# 04-Control_Circuit.net
KiCad netlist of a schematic drawn in Altium Designer
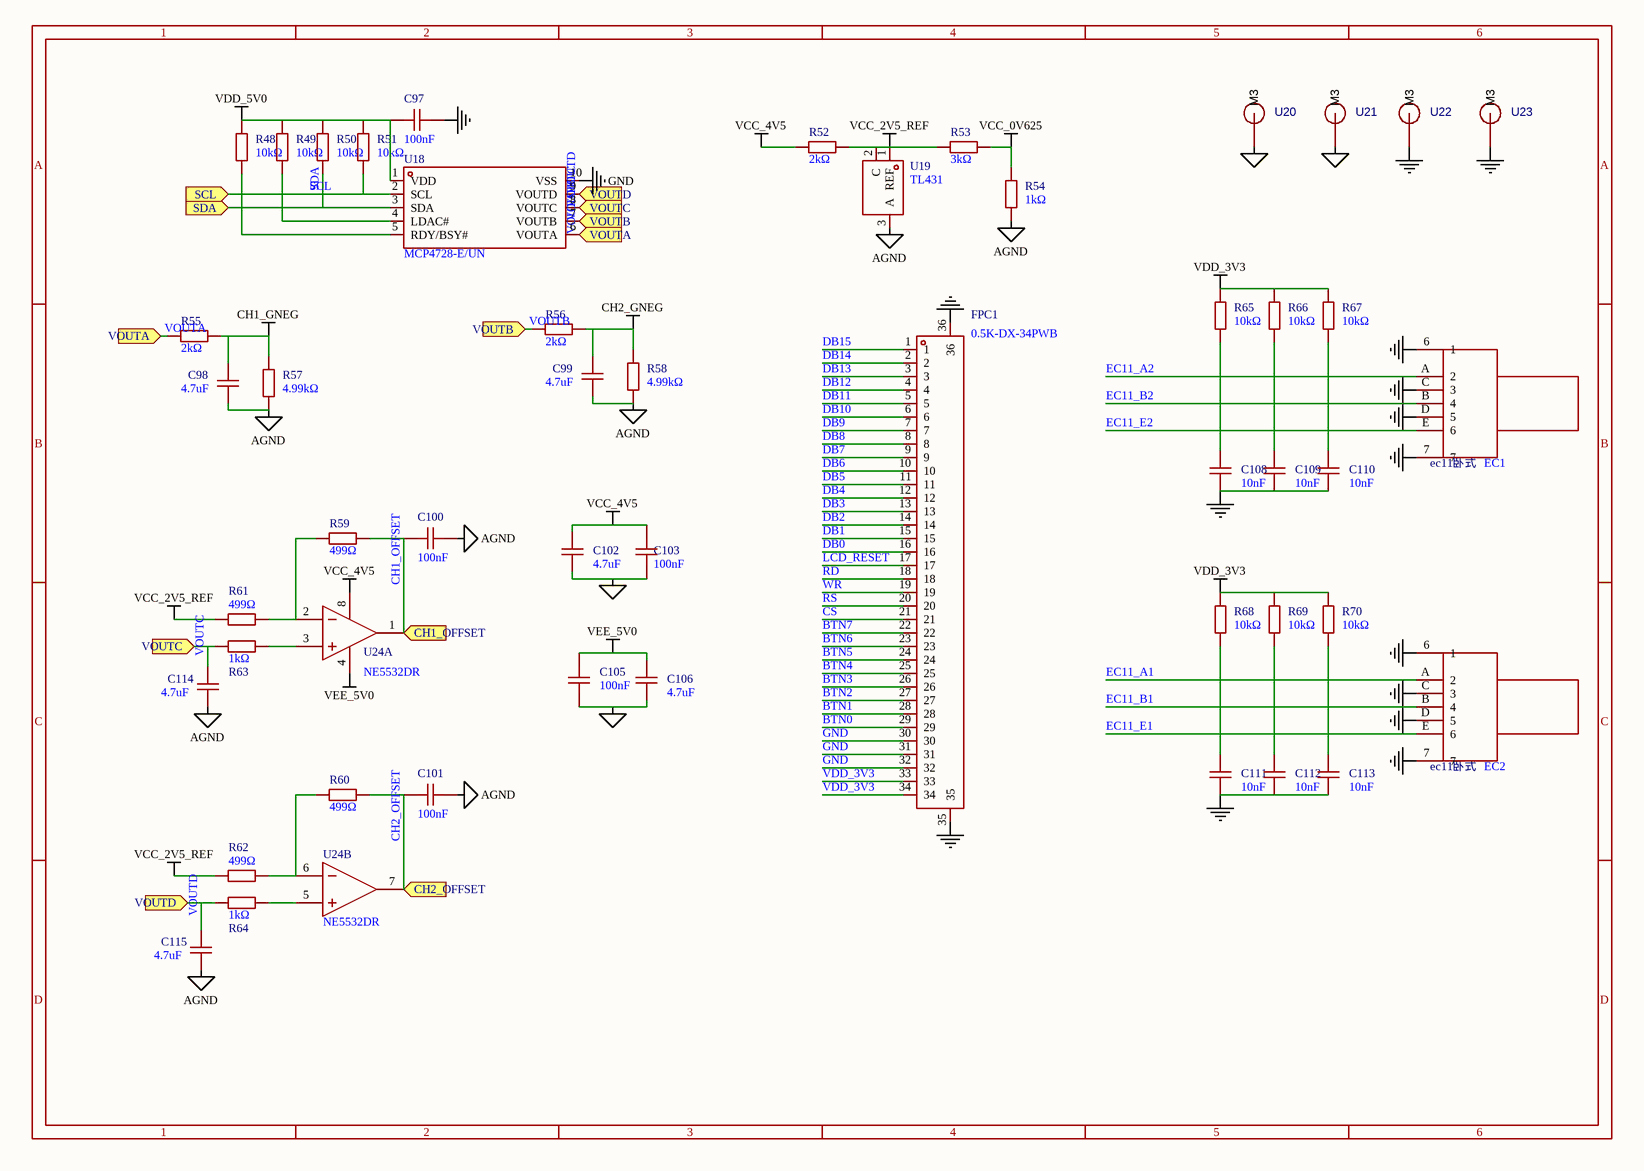
[diagram p0: 04-Control Circuit.schdoc]

(export (version "E")
  (design (tool "Eeschema 10.0.6"))
  (components
    (comp (ref "C97")
      (value "100nF")
      (footprint "C0603")
      (fields
        (field (name "MANUFACTURER") "HRE(芯声)")
        (field (name "MANUFACTURER PART") "CGA0603X7R104K500JT")
        (field (name "TOLERANCE") "±10%")
      )
      (libsource (lib "altium-import") (part "root_2_CGA0603X7R104K500JT_"))
    )
    (comp (ref "C98")
      (value "4.7uF")
      (footprint "C0603")
      (fields
        (field (name "MANUFACTURER") "SAMSUNG(三星)")
        (field (name "MANUFACTURER PART") "CL10A475KO8NNNC")
        (field (name "TOLERANCE") "±10%")
      )
      (libsource (lib "altium-import") (part "root_1_CL10A475KO8NNNC_"))
    )
    (comp (ref "C99")
      (value "4.7uF")
      (footprint "C0603")
      (fields
        (field (name "MANUFACTURER") "SAMSUNG(三星)")
        (field (name "MANUFACTURER PART") "CL10A475KO8NNNC")
        (field (name "TOLERANCE") "±10%")
      )
      (libsource (lib "altium-import") (part "root_1_CL10A475KO8NNNC_"))
    )
    (comp (ref "C100")
      (value "100nF")
      (footprint "C0603")
      (fields
        (field (name "MANUFACTURER") "HRE(芯声)")
        (field (name "MANUFACTURER PART") "CGA0603X7R104K500JT")
        (field (name "TOLERANCE") "±10%")
      )
      (libsource (lib "altium-import") (part "root_2_CGA0603X7R104K500JT_"))
    )
    (comp (ref "C101")
      (value "100nF")
      (footprint "C0603")
      (fields
        (field (name "MANUFACTURER") "HRE(芯声)")
        (field (name "MANUFACTURER PART") "CGA0603X7R104K500JT")
        (field (name "TOLERANCE") "±10%")
      )
      (libsource (lib "altium-import") (part "root_2_CGA0603X7R104K500JT_"))
    )
    (comp (ref "C102")
      (value "4.7uF")
      (footprint "C0603")
      (fields
        (field (name "MANUFACTURER") "SAMSUNG(三星)")
        (field (name "MANUFACTURER PART") "CL10A475KO8NNNC")
        (field (name "TOLERANCE") "±10%")
      )
      (libsource (lib "altium-import") (part "root_1_CL10A475KO8NNNC_"))
    )
    (comp (ref "C103")
      (value "100nF")
      (footprint "C0603")
      (fields
        (field (name "MANUFACTURER") "HRE(芯声)")
        (field (name "MANUFACTURER PART") "CGA0603X7R104K500JT")
        (field (name "TOLERANCE") "±10%")
      )
      (libsource (lib "altium-import") (part "root_1_CGA0603X7R104K500JT_"))
    )
    (comp (ref "C105")
      (value "100nF")
      (footprint "C0603")
      (fields
        (field (name "MANUFACTURER") "HRE(芯声)")
        (field (name "MANUFACTURER PART") "CGA0603X7R104K500JT")
        (field (name "TOLERANCE") "±10%")
      )
      (libsource (lib "altium-import") (part "root_1_CGA0603X7R104K500JT_"))
    )
    (comp (ref "C106")
      (value "4.7uF")
      (footprint "C0603")
      (fields
        (field (name "MANUFACTURER") "SAMSUNG(三星)")
        (field (name "MANUFACTURER PART") "CL10A475KO8NNNC")
        (field (name "TOLERANCE") "±10%")
      )
      (libsource (lib "altium-import") (part "root_1_CL10A475KO8NNNC_"))
    )
    (comp (ref "C108")
      (value "10nF")
      (footprint "C0603")
      (fields
        (field (name "MANUFACTURER") "YAGEO(国巨)")
        (field (name "MANUFACTURER PART") "CC0603KRX7R9BB103")
        (field (name "TOLERANCE") "±10%")
      )
      (libsource (lib "altium-import") (part "root_1_CC0603KRX7R9BB103_"))
    )
    (comp (ref "C109")
      (value "10nF")
      (footprint "C0603")
      (fields
        (field (name "MANUFACTURER") "YAGEO(国巨)")
        (field (name "MANUFACTURER PART") "CC0603KRX7R9BB103")
        (field (name "TOLERANCE") "±10%")
      )
      (libsource (lib "altium-import") (part "root_1_CC0603KRX7R9BB103_"))
    )
    (comp (ref "C110")
      (value "10nF")
      (footprint "C0603")
      (fields
        (field (name "MANUFACTURER") "YAGEO(国巨)")
        (field (name "MANUFACTURER PART") "CC0603KRX7R9BB103")
        (field (name "TOLERANCE") "±10%")
      )
      (libsource (lib "altium-import") (part "root_1_CC0603KRX7R9BB103_"))
    )
    (comp (ref "C111")
      (value "10nF")
      (footprint "C0603")
      (fields
        (field (name "MANUFACTURER") "YAGEO(国巨)")
        (field (name "MANUFACTURER PART") "CC0603KRX7R9BB103")
        (field (name "TOLERANCE") "±10%")
      )
      (libsource (lib "altium-import") (part "root_1_CC0603KRX7R9BB103_"))
    )
    (comp (ref "C112")
      (value "10nF")
      (footprint "C0603")
      (fields
        (field (name "MANUFACTURER") "YAGEO(国巨)")
        (field (name "MANUFACTURER PART") "CC0603KRX7R9BB103")
        (field (name "TOLERANCE") "±10%")
      )
      (libsource (lib "altium-import") (part "root_1_CC0603KRX7R9BB103_"))
    )
    (comp (ref "C113")
      (value "10nF")
      (footprint "C0603")
      (fields
        (field (name "MANUFACTURER") "YAGEO(国巨)")
        (field (name "MANUFACTURER PART") "CC0603KRX7R9BB103")
        (field (name "TOLERANCE") "±10%")
      )
      (libsource (lib "altium-import") (part "root_1_CC0603KRX7R9BB103_"))
    )
    (comp (ref "C114")
      (value "4.7uF")
      (footprint "C0603")
      (fields
        (field (name "MANUFACTURER") "SAMSUNG(三星)")
        (field (name "MANUFACTURER PART") "CL10A475KO8NNNC")
        (field (name "TOLERANCE") "±10%")
      )
      (libsource (lib "altium-import") (part "root_1_CL10A475KO8NNNC_"))
    )
    (comp (ref "C115")
      (value "4.7uF")
      (footprint "C0603")
      (fields
        (field (name "MANUFACTURER") "SAMSUNG(三星)")
        (field (name "MANUFACTURER PART") "CL10A475KO8NNNC")
        (field (name "TOLERANCE") "±10%")
      )
      (libsource (lib "altium-import") (part "root_1_CL10A475KO8NNNC_"))
    )
    (comp (ref "EC1")
      (value "~")
      (footprint "ec11卧式立式编码器")
      (fields (field (name "DEVICE") "ec11卧式"))
      (libsource (lib "altium-import") (part "root_0_ec11卧式_"))
    )
    (comp (ref "EC2")
      (value "~")
      (footprint "ec11卧式立式编码器")
      (fields (field (name "DEVICE") "ec11卧式"))
      (libsource (lib "altium-import") (part "root_0_ec11卧式_"))
    )
    (comp (ref "FPC1")
      (value "0.5K-DX-34PWB")
      (footprint "FPC-SMD_F0502-B-34-15T-R")
      (fields (field (name "MANUFACTURER") "HDGC(华德共创)"))
      (libsource (lib "altium-import") (part "root_0_0.5K-DX-34PWB_"))
    )
    (comp (ref "R48")
      (value "10kΩ")
      (footprint "R0603")
      (fields
        (field (name "MANUFACTURER") "UNI-ROYAL(厚声)")
        (field (name "MANUFACTURER PART") "0603WAF1002T5E")
        (field (name "TOLERANCE") "±1%")
      )
      (libsource (lib "altium-import") (part "root_1_0603WAF1002T5E_"))
    )
    (comp (ref "R49")
      (value "10kΩ")
      (footprint "R0603")
      (fields
        (field (name "MANUFACTURER") "UNI-ROYAL(厚声)")
        (field (name "MANUFACTURER PART") "0603WAF1002T5E")
        (field (name "TOLERANCE") "±1%")
      )
      (libsource (lib "altium-import") (part "root_1_0603WAF1002T5E_"))
    )
    (comp (ref "R50")
      (value "10kΩ")
      (footprint "R0603")
      (fields
        (field (name "MANUFACTURER") "UNI-ROYAL(厚声)")
        (field (name "MANUFACTURER PART") "0603WAF1002T5E")
        (field (name "TOLERANCE") "±1%")
      )
      (libsource (lib "altium-import") (part "root_1_0603WAF1002T5E_"))
    )
    (comp (ref "R51")
      (value "10kΩ")
      (footprint "R0603")
      (fields
        (field (name "MANUFACTURER") "UNI-ROYAL(厚声)")
        (field (name "MANUFACTURER PART") "0603WAF1002T5E")
        (field (name "TOLERANCE") "±1%")
      )
      (libsource (lib "altium-import") (part "root_1_0603WAF1002T5E_"))
    )
    (comp (ref "R52")
      (value "2kΩ")
      (footprint "R0603")
      (fields
        (field (name "MANUFACTURER") "UNI-ROYAL(厚声)")
        (field (name "MANUFACTURER PART") "0603WAF2001T5E")
        (field (name "TOLERANCE") "±1%")
      )
      (libsource (lib "altium-import") (part "root_2_0603WAF2001T5E_"))
    )
    (comp (ref "R53")
      (value "3kΩ")
      (footprint "R0603")
      (fields
        (field (name "MANUFACTURER") "UNI-ROYAL(厚声)")
        (field (name "MANUFACTURER PART") "0603WAF3001T5E")
        (field (name "TOLERANCE") "±1%")
      )
      (libsource (lib "altium-import") (part "root_0_0603WAF3001T5E_"))
    )
    (comp (ref "R54")
      (value "1kΩ")
      (footprint "R0603")
      (fields
        (field (name "MANUFACTURER") "UNI-ROYAL(厚声)")
        (field (name "MANUFACTURER PART") "0603WAF1001T5E")
        (field (name "TOLERANCE") "±1%")
      )
      (libsource (lib "altium-import") (part "root_1_0603WAF1001T5E_"))
    )
    (comp (ref "R55")
      (value "2kΩ")
      (footprint "R0603")
      (fields
        (field (name "MANUFACTURER") "UNI-ROYAL(厚声)")
        (field (name "MANUFACTURER PART") "0603WAF2001T5E")
        (field (name "TOLERANCE") "±1%")
      )
      (libsource (lib "altium-import") (part "root_2_0603WAF2001T5E_"))
    )
    (comp (ref "R56")
      (value "2kΩ")
      (footprint "R0603")
      (fields
        (field (name "MANUFACTURER") "UNI-ROYAL(厚声)")
        (field (name "MANUFACTURER PART") "0603WAF2001T5E")
        (field (name "TOLERANCE") "±1%")
      )
      (libsource (lib "altium-import") (part "root_2_0603WAF2001T5E_"))
    )
    (comp (ref "R57")
      (value "4.99kΩ")
      (footprint "R0603")
      (fields
        (field (name "MANUFACTURER") "UNI-ROYAL(厚声)")
        (field (name "MANUFACTURER PART") "0603WAF4991T5E")
        (field (name "TOLERANCE") "±1%")
      )
      (libsource (lib "altium-import") (part "root_1_0603WAF4991T5E_"))
    )
    (comp (ref "R58")
      (value "4.99kΩ")
      (footprint "R0603")
      (fields
        (field (name "MANUFACTURER") "UNI-ROYAL(厚声)")
        (field (name "MANUFACTURER PART") "0603WAF4991T5E")
        (field (name "TOLERANCE") "±1%")
      )
      (libsource (lib "altium-import") (part "root_1_0603WAF4991T5E_"))
    )
    (comp (ref "R59")
      (value "499Ω")
      (footprint "R0603")
      (fields
        (field (name "MANUFACTURER") "UNI-ROYAL(厚声)")
        (field (name "MANUFACTURER PART") "0603WAF4990T5E")
        (field (name "TOLERANCE") "±1%")
      )
      (libsource (lib "altium-import") (part "root_0_0603WAF4990T5E_"))
    )
    (comp (ref "R60")
      (value "499Ω")
      (footprint "R0603")
      (fields
        (field (name "MANUFACTURER") "UNI-ROYAL(厚声)")
        (field (name "MANUFACTURER PART") "0603WAF4990T5E")
        (field (name "TOLERANCE") "±1%")
      )
      (libsource (lib "altium-import") (part "root_0_0603WAF4990T5E_"))
    )
    (comp (ref "R61")
      (value "499Ω")
      (footprint "R0603")
      (fields
        (field (name "MANUFACTURER") "UNI-ROYAL(厚声)")
        (field (name "MANUFACTURER PART") "0603WAF4990T5E")
        (field (name "TOLERANCE") "±1%")
      )
      (libsource (lib "altium-import") (part "root_0_0603WAF4990T5E_"))
    )
    (comp (ref "R62")
      (value "499Ω")
      (footprint "R0603")
      (fields
        (field (name "MANUFACTURER") "UNI-ROYAL(厚声)")
        (field (name "MANUFACTURER PART") "0603WAF4990T5E")
        (field (name "TOLERANCE") "±1%")
      )
      (libsource (lib "altium-import") (part "root_0_0603WAF4990T5E_"))
    )
    (comp (ref "R63")
      (value "1kΩ")
      (footprint "R0603")
      (fields
        (field (name "MANUFACTURER") "UNI-ROYAL(厚声)")
        (field (name "MANUFACTURER PART") "0603WAF1001T5E")
        (field (name "TOLERANCE") "±1%")
      )
      (libsource (lib "altium-import") (part "root_0_0603WAF1001T5E_"))
    )
    (comp (ref "R64")
      (value "1kΩ")
      (footprint "R0603")
      (fields
        (field (name "MANUFACTURER") "UNI-ROYAL(厚声)")
        (field (name "MANUFACTURER PART") "0603WAF1001T5E")
        (field (name "TOLERANCE") "±1%")
      )
      (libsource (lib "altium-import") (part "root_0_0603WAF1001T5E_"))
    )
    (comp (ref "R65")
      (value "10kΩ")
      (footprint "R0603")
      (fields
        (field (name "MANUFACTURER") "UNI-ROYAL(厚声)")
        (field (name "MANUFACTURER PART") "0603WAF1002T5E")
        (field (name "TOLERANCE") "±1%")
      )
      (libsource (lib "altium-import") (part "root_1_0603WAF1002T5E_"))
    )
    (comp (ref "R66")
      (value "10kΩ")
      (footprint "R0603")
      (fields
        (field (name "MANUFACTURER") "UNI-ROYAL(厚声)")
        (field (name "MANUFACTURER PART") "0603WAF1002T5E")
        (field (name "TOLERANCE") "±1%")
      )
      (libsource (lib "altium-import") (part "root_1_0603WAF1002T5E_"))
    )
    (comp (ref "R67")
      (value "10kΩ")
      (footprint "R0603")
      (fields
        (field (name "MANUFACTURER") "UNI-ROYAL(厚声)")
        (field (name "MANUFACTURER PART") "0603WAF1002T5E")
        (field (name "TOLERANCE") "±1%")
      )
      (libsource (lib "altium-import") (part "root_1_0603WAF1002T5E_"))
    )
    (comp (ref "R68")
      (value "10kΩ")
      (footprint "R0603")
      (fields
        (field (name "MANUFACTURER") "UNI-ROYAL(厚声)")
        (field (name "MANUFACTURER PART") "0603WAF1002T5E")
        (field (name "TOLERANCE") "±1%")
      )
      (libsource (lib "altium-import") (part "root_1_0603WAF1002T5E_"))
    )
    (comp (ref "R69")
      (value "10kΩ")
      (footprint "R0603")
      (fields
        (field (name "MANUFACTURER") "UNI-ROYAL(厚声)")
        (field (name "MANUFACTURER PART") "0603WAF1002T5E")
        (field (name "TOLERANCE") "±1%")
      )
      (libsource (lib "altium-import") (part "root_1_0603WAF1002T5E_"))
    )
    (comp (ref "R70")
      (value "10kΩ")
      (footprint "R0603")
      (fields
        (field (name "MANUFACTURER") "UNI-ROYAL(厚声)")
        (field (name "MANUFACTURER PART") "0603WAF1002T5E")
        (field (name "TOLERANCE") "±1%")
      )
      (libsource (lib "altium-import") (part "root_1_0603WAF1002T5E_"))
    )
    (comp (ref "U18")
      (value "MCP4728-E/UN")
      (footprint "MSOP-10_L3.0-W3.0-P0.50-LS5.0-TL")
      (fields (field (name "MANUFACTURER") "MICROCHIP(美国微芯)"))
      (libsource (lib "altium-import") (part "root_0_MCP4728-E/UN_"))
    )
    (comp (ref "U19")
      (value "TL431")
      (footprint "SOT-23-3_L3.0-W1.7-P0.95-LS2.9-BR")
      (fields (field (name "MANUFACTURER") "Hottech(合科泰)"))
      (libsource (lib "altium-import") (part "root_2_TL431_C181103_"))
    )
    (comp (ref "U20") (value "~") (footprint "M3螺柱") (libsource (lib "altium-import") (part "root_3_M3螺柱_")))
    (comp (ref "U21") (value "~") (footprint "M3螺柱") (libsource (lib "altium-import") (part "root_3_M3螺柱_")))
    (comp (ref "U22") (value "~") (footprint "M3螺柱") (libsource (lib "altium-import") (part "root_3_M3螺柱_")))
    (comp (ref "U23") (value "~") (footprint "M3螺柱") (libsource (lib "altium-import") (part "root_3_M3螺柱_")))
    (comp (ref "U24")
      (value "NE5532DR")
      (footprint "SOIC-8_L4.9-W3.9-P1.27-LS6.0-BL")
      (fields (field (name "MANUFACTURER") "TI(德州仪器)"))
      (libsource (lib "altium-import") (part "root_0_NE5532DR_"))
    )
  )
  (nets
    (net (code "1") (name "/BTN0") (class "Default")
      (node (ref "FPC1") (pin "29") (pinfunction "29_29") (pintype "passive"))
    )
    (net (code "2") (name "/BTN1") (class "Default")
      (node (ref "FPC1") (pin "28") (pinfunction "28_28") (pintype "passive"))
    )
    (net (code "3") (name "/BTN2") (class "Default")
      (node (ref "FPC1") (pin "27") (pinfunction "27_27") (pintype "passive"))
    )
    (net (code "4") (name "/BTN3") (class "Default")
      (node (ref "FPC1") (pin "26") (pinfunction "26_26") (pintype "passive"))
    )
    (net (code "5") (name "/BTN4") (class "Default")
      (node (ref "FPC1") (pin "25") (pinfunction "25_25") (pintype "passive"))
    )
    (net (code "6") (name "/BTN5") (class "Default")
      (node (ref "FPC1") (pin "24") (pinfunction "24_24") (pintype "passive"))
    )
    (net (code "7") (name "/BTN6") (class "Default")
      (node (ref "FPC1") (pin "23") (pinfunction "23_23") (pintype "passive"))
    )
    (net (code "8") (name "/BTN7") (class "Default")
      (node (ref "FPC1") (pin "22") (pinfunction "22_22") (pintype "passive"))
    )
    (net (code "9") (name "/CH1_OFFSET") (class "Default")
      (node (ref "C100") (pin "2") (pinfunction "2_2") (pintype "passive"))
      (node (ref "R59") (pin "2") (pinfunction "2_2") (pintype "passive"))
      (node (ref "U24") (pin "1") (pinfunction "OUT1_1") (pintype "passive"))
    )
    (net (code "10") (name "/CH2_OFFSET") (class "Default")
      (node (ref "C101") (pin "2") (pinfunction "2_2") (pintype "passive"))
      (node (ref "R60") (pin "2") (pinfunction "2_2") (pintype "passive"))
      (node (ref "U24") (pin "7") (pinfunction "OUT2_7") (pintype "passive"))
    )
    (net (code "11") (name "/CS") (class "Default")
      (node (ref "FPC1") (pin "21") (pinfunction "21_21") (pintype "passive"))
    )
    (net (code "12") (name "/DB0") (class "Default")
      (node (ref "FPC1") (pin "16") (pinfunction "16_16") (pintype "passive"))
    )
    (net (code "13") (name "/DB1") (class "Default")
      (node (ref "FPC1") (pin "15") (pinfunction "15_15") (pintype "passive"))
    )
    (net (code "14") (name "/DB2") (class "Default")
      (node (ref "FPC1") (pin "14") (pinfunction "14_14") (pintype "passive"))
    )
    (net (code "15") (name "/DB3") (class "Default")
      (node (ref "FPC1") (pin "13") (pinfunction "13_13") (pintype "passive"))
    )
    (net (code "16") (name "/DB4") (class "Default")
      (node (ref "FPC1") (pin "12") (pinfunction "12_12") (pintype "passive"))
    )
    (net (code "17") (name "/DB5") (class "Default")
      (node (ref "FPC1") (pin "11") (pinfunction "11_11") (pintype "passive"))
    )
    (net (code "18") (name "/DB6") (class "Default")
      (node (ref "FPC1") (pin "10") (pinfunction "10_10") (pintype "passive"))
    )
    (net (code "19") (name "/DB7") (class "Default")
      (node (ref "FPC1") (pin "9") (pinfunction "9_9") (pintype "passive"))
    )
    (net (code "20") (name "/DB8") (class "Default")
      (node (ref "FPC1") (pin "8") (pinfunction "8_8") (pintype "passive"))
    )
    (net (code "21") (name "/DB9") (class "Default")
      (node (ref "FPC1") (pin "7") (pinfunction "7_7") (pintype "passive"))
    )
    (net (code "22") (name "/DB10") (class "Default")
      (node (ref "FPC1") (pin "6") (pinfunction "6_6") (pintype "passive"))
    )
    (net (code "23") (name "/DB11") (class "Default")
      (node (ref "FPC1") (pin "5") (pinfunction "5_5") (pintype "passive"))
    )
    (net (code "24") (name "/DB12") (class "Default")
      (node (ref "FPC1") (pin "4") (pinfunction "4_4") (pintype "passive"))
    )
    (net (code "25") (name "/DB13") (class "Default")
      (node (ref "FPC1") (pin "3") (pinfunction "3_3") (pintype "passive"))
    )
    (net (code "26") (name "/DB14") (class "Default")
      (node (ref "FPC1") (pin "2") (pinfunction "2_2") (pintype "passive"))
    )
    (net (code "27") (name "/DB15") (class "Default")
      (node (ref "FPC1") (pin "1") (pinfunction "1_1") (pintype "passive"))
    )
    (net (code "28") (name "/EC11_A1") (class "Default")
      (node (ref "C111") (pin "2") (pinfunction "2_2") (pintype "passive"))
      (node (ref "EC2") (pin "A") (pinfunction "2_A") (pintype "passive"))
      (node (ref "R68") (pin "1") (pinfunction "1_1") (pintype "passive"))
    )
    (net (code "29") (name "/EC11_A2") (class "Default")
      (node (ref "C108") (pin "2") (pinfunction "2_2") (pintype "passive"))
      (node (ref "EC1") (pin "A") (pinfunction "2_A") (pintype "passive"))
      (node (ref "R65") (pin "1") (pinfunction "1_1") (pintype "passive"))
    )
    (net (code "30") (name "/EC11_B1") (class "Default")
      (node (ref "C112") (pin "2") (pinfunction "2_2") (pintype "passive"))
      (node (ref "EC2") (pin "B") (pinfunction "4_B") (pintype "passive"))
      (node (ref "R69") (pin "1") (pinfunction "1_1") (pintype "passive"))
    )
    (net (code "31") (name "/EC11_B2") (class "Default")
      (node (ref "C109") (pin "2") (pinfunction "2_2") (pintype "passive"))
      (node (ref "EC1") (pin "B") (pinfunction "4_B") (pintype "passive"))
      (node (ref "R66") (pin "1") (pinfunction "1_1") (pintype "passive"))
    )
    (net (code "32") (name "/EC11_E1") (class "Default")
      (node (ref "C113") (pin "2") (pinfunction "2_2") (pintype "passive"))
      (node (ref "EC2") (pin "E") (pinfunction "6_E") (pintype "passive"))
      (node (ref "R70") (pin "1") (pinfunction "1_1") (pintype "passive"))
    )
    (net (code "33") (name "/EC11_E2") (class "Default")
      (node (ref "C110") (pin "2") (pinfunction "2_2") (pintype "passive"))
      (node (ref "EC1") (pin "E") (pinfunction "6_E") (pintype "passive"))
      (node (ref "R67") (pin "1") (pinfunction "1_1") (pintype "passive"))
    )
    (net (code "34") (name "/LCD_RESET") (class "Default")
      (node (ref "FPC1") (pin "17") (pinfunction "17_17") (pintype "passive"))
    )
    (net (code "35") (name "/RD") (class "Default")
      (node (ref "FPC1") (pin "18") (pinfunction "18_18") (pintype "passive"))
    )
    (net (code "36") (name "/RS") (class "Default")
      (node (ref "FPC1") (pin "20") (pinfunction "20_20") (pintype "passive"))
    )
    (net (code "37") (name "/SCL") (class "Default")
      (node (ref "R51") (pin "1") (pinfunction "1_1") (pintype "passive"))
      (node (ref "U18") (pin "2") (pinfunction "SCL_2") (pintype "passive"))
    )
    (net (code "38") (name "/SDA") (class "Default")
      (node (ref "R50") (pin "1") (pinfunction "1_1") (pintype "passive"))
      (node (ref "U18") (pin "3") (pinfunction "SDA_3") (pintype "passive"))
    )
    (net (code "39") (name "/VOUTA") (class "Default")
      (node (ref "R55") (pin "2") (pinfunction "2_2") (pintype "passive"))
      (node (ref "U18") (pin "6") (pinfunction "VOUTA_6") (pintype "passive"))
    )
    (net (code "40") (name "/VOUTB") (class "Default")
      (node (ref "R56") (pin "2") (pinfunction "2_2") (pintype "passive"))
      (node (ref "U18") (pin "7") (pinfunction "VOUTB_7") (pintype "passive"))
    )
    (net (code "41") (name "/VOUTC") (class "Default")
      (node (ref "C114") (pin "2") (pinfunction "2_2") (pintype "passive"))
      (node (ref "R63") (pin "1") (pinfunction "1_1") (pintype "passive"))
      (node (ref "U18") (pin "8") (pinfunction "VOUTC_8") (pintype "passive"))
    )
    (net (code "42") (name "/VOUTD") (class "Default")
      (node (ref "C115") (pin "2") (pinfunction "2_2") (pintype "passive"))
      (node (ref "R64") (pin "1") (pinfunction "1_1") (pintype "passive"))
      (node (ref "U18") (pin "9") (pinfunction "VOUTD_9") (pintype "passive"))
    )
    (net (code "43") (name "/WR") (class "Default")
      (node (ref "FPC1") (pin "19") (pinfunction "19_19") (pintype "passive"))
    )
    (net (code "44") (name "AGND") (class "Default")
      (node (ref "C100") (pin "1") (pinfunction "1_1") (pintype "passive"))
      (node (ref "C101") (pin "1") (pinfunction "1_1") (pintype "passive"))
      (node (ref "C102") (pin "1") (pinfunction "1_1") (pintype "passive"))
      (node (ref "C103") (pin "1") (pinfunction "1_1") (pintype "passive"))
      (node (ref "C105") (pin "1") (pinfunction "1_1") (pintype "passive"))
      (node (ref "C106") (pin "1") (pinfunction "1_1") (pintype "passive"))
      (node (ref "C114") (pin "1") (pinfunction "1_1") (pintype "passive"))
      (node (ref "C115") (pin "1") (pinfunction "1_1") (pintype "passive"))
      (node (ref "C98") (pin "1") (pinfunction "1_1") (pintype "passive"))
      (node (ref "C99") (pin "1") (pinfunction "1_1") (pintype "passive"))
      (node (ref "R54") (pin "1") (pinfunction "1_1") (pintype "passive"))
      (node (ref "R57") (pin "1") (pinfunction "1_1") (pintype "passive"))
      (node (ref "R58") (pin "1") (pinfunction "1_1") (pintype "passive"))
      (node (ref "U19") (pin "3") (pinfunction "A_3") (pintype "passive"))
      (node (ref "U20") (pin "1") (pinfunction "M3_1") (pintype "passive"))
      (node (ref "U21") (pin "1") (pinfunction "M3_1") (pintype "passive"))
    )
    (net (code "45") (name "CH1_GNEG") (class "Default")
      (node (ref "C98") (pin "2") (pinfunction "2_2") (pintype "passive"))
      (node (ref "R55") (pin "1") (pinfunction "1_1") (pintype "passive"))
      (node (ref "R57") (pin "2") (pinfunction "2_2") (pintype "passive"))
    )
    (net (code "46") (name "CH2_GNEG") (class "Default")
      (node (ref "C99") (pin "2") (pinfunction "2_2") (pintype "passive"))
      (node (ref "R56") (pin "1") (pinfunction "1_1") (pintype "passive"))
      (node (ref "R58") (pin "2") (pinfunction "2_2") (pintype "passive"))
    )
    (net (code "47") (name "GND") (class "Default")
      (node (ref "C108") (pin "1") (pinfunction "1_1") (pintype "passive"))
      (node (ref "C109") (pin "1") (pinfunction "1_1") (pintype "passive"))
      (node (ref "C110") (pin "1") (pinfunction "1_1") (pintype "passive"))
      (node (ref "C111") (pin "1") (pinfunction "1_1") (pintype "passive"))
      (node (ref "C112") (pin "1") (pinfunction "1_1") (pintype "passive"))
      (node (ref "C113") (pin "1") (pinfunction "1_1") (pintype "passive"))
      (node (ref "C97") (pin "1") (pinfunction "1_1") (pintype "passive"))
      (node (ref "EC1") (pin "6") (pinfunction "1_6") (pintype "passive"))
      (node (ref "EC1") (pin "7") (pinfunction "7_7") (pintype "passive"))
      (node (ref "EC1") (pin "C") (pinfunction "3_C") (pintype "passive"))
      (node (ref "EC1") (pin "D") (pinfunction "5_D") (pintype "passive"))
      (node (ref "EC2") (pin "6") (pinfunction "1_6") (pintype "passive"))
      (node (ref "EC2") (pin "7") (pinfunction "7_7") (pintype "passive"))
      (node (ref "EC2") (pin "C") (pinfunction "3_C") (pintype "passive"))
      (node (ref "EC2") (pin "D") (pinfunction "5_D") (pintype "passive"))
      (node (ref "FPC1") (pin "30") (pinfunction "30_30") (pintype "passive"))
      (node (ref "FPC1") (pin "31") (pinfunction "31_31") (pintype "passive"))
      (node (ref "FPC1") (pin "32") (pinfunction "32_32") (pintype "passive"))
      (node (ref "FPC1") (pin "35") (pinfunction "35_35") (pintype "passive"))
      (node (ref "FPC1") (pin "36") (pinfunction "36_36") (pintype "passive"))
      (node (ref "U18") (pin "10") (pinfunction "VSS_10") (pintype "passive"))
      (node (ref "U22") (pin "1") (pinfunction "M3_1") (pintype "passive"))
      (node (ref "U23") (pin "1") (pinfunction "M3_1") (pintype "passive"))
    )
    (net (code "48") (name "Net-(U18-LDAC#)") (class "Default")
      (node (ref "R49") (pin "1") (pinfunction "1_1") (pintype "passive"))
      (node (ref "U18") (pin "4") (pinfunction "LDAC#_4") (pintype "passive"))
    )
    (net (code "49") (name "Net-(U18-RDY{slash}BSY#)") (class "Default")
      (node (ref "R48") (pin "1") (pinfunction "1_1") (pintype "passive"))
      (node (ref "U18") (pin "5") (pinfunction "RDY/BSY#_5") (pintype "passive"))
    )
    (net (code "50") (name "Net-(U24A-IN1+)") (class "Default")
      (node (ref "R63") (pin "2") (pinfunction "2_2") (pintype "passive"))
      (node (ref "U24") (pin "3") (pinfunction "IN1+_3") (pintype "passive"))
    )
    (net (code "51") (name "Net-(U24A-IN1-)") (class "Default")
      (node (ref "R59") (pin "1") (pinfunction "1_1") (pintype "passive"))
      (node (ref "R61") (pin "2") (pinfunction "2_2") (pintype "passive"))
      (node (ref "U24") (pin "2") (pinfunction "IN1-_2") (pintype "passive"))
    )
    (net (code "52") (name "Net-(U24B-IN2+)") (class "Default")
      (node (ref "R64") (pin "2") (pinfunction "2_2") (pintype "passive"))
      (node (ref "U24") (pin "5") (pinfunction "IN2+_5") (pintype "passive"))
    )
    (net (code "53") (name "Net-(U24B-IN2-)") (class "Default")
      (node (ref "R60") (pin "1") (pinfunction "1_1") (pintype "passive"))
      (node (ref "R62") (pin "2") (pinfunction "2_2") (pintype "passive"))
      (node (ref "U24") (pin "6") (pinfunction "IN2-_6") (pintype "passive"))
    )
    (net (code "54") (name "VCC_0V625") (class "Default")
      (node (ref "R53") (pin "2") (pinfunction "2_2") (pintype "passive"))
      (node (ref "R54") (pin "2") (pinfunction "2_2") (pintype "passive"))
    )
    (net (code "55") (name "VCC_2V5_REF") (class "Default")
      (node (ref "R52") (pin "1") (pinfunction "1_1") (pintype "passive"))
      (node (ref "R53") (pin "1") (pinfunction "1_1") (pintype "passive"))
      (node (ref "R61") (pin "1") (pinfunction "1_1") (pintype "passive"))
      (node (ref "R62") (pin "1") (pinfunction "1_1") (pintype "passive"))
      (node (ref "U19") (pin "1") (pinfunction "REF_1") (pintype "passive"))
      (node (ref "U19") (pin "2") (pinfunction "C_2") (pintype "passive"))
    )
    (net (code "56") (name "VCC_4V5") (class "Default")
      (node (ref "C102") (pin "2") (pinfunction "2_2") (pintype "passive"))
      (node (ref "C103") (pin "2") (pinfunction "2_2") (pintype "passive"))
      (node (ref "R52") (pin "2") (pinfunction "2_2") (pintype "passive"))
      (node (ref "U24") (pin "8") (pinfunction "VCC+_8") (pintype "passive"))
    )
    (net (code "57") (name "VDD_3V3") (class "Default")
      (node (ref "FPC1") (pin "33") (pinfunction "33_33") (pintype "passive"))
      (node (ref "FPC1") (pin "34") (pinfunction "34_34") (pintype "passive"))
      (node (ref "R65") (pin "2") (pinfunction "2_2") (pintype "passive"))
      (node (ref "R66") (pin "2") (pinfunction "2_2") (pintype "passive"))
      (node (ref "R67") (pin "2") (pinfunction "2_2") (pintype "passive"))
      (node (ref "R68") (pin "2") (pinfunction "2_2") (pintype "passive"))
      (node (ref "R69") (pin "2") (pinfunction "2_2") (pintype "passive"))
      (node (ref "R70") (pin "2") (pinfunction "2_2") (pintype "passive"))
    )
    (net (code "58") (name "VDD_5V0") (class "Default")
      (node (ref "C97") (pin "2") (pinfunction "2_2") (pintype "passive"))
      (node (ref "R48") (pin "2") (pinfunction "2_2") (pintype "passive"))
      (node (ref "R49") (pin "2") (pinfunction "2_2") (pintype "passive"))
      (node (ref "R50") (pin "2") (pinfunction "2_2") (pintype "passive"))
      (node (ref "R51") (pin "2") (pinfunction "2_2") (pintype "passive"))
      (node (ref "U18") (pin "1") (pinfunction "VDD_1") (pintype "passive"))
    )
    (net (code "59") (name "VEE_5V0") (class "Default")
      (node (ref "C105") (pin "2") (pinfunction "2_2") (pintype "passive"))
      (node (ref "C106") (pin "2") (pinfunction "2_2") (pintype "passive"))
      (node (ref "U24") (pin "4") (pinfunction "VCC-/GND_4") (pintype "passive"))
    )
  )
)
